# power-control-v2.net
KiCad netlist of a schematic drawn in EAGLE
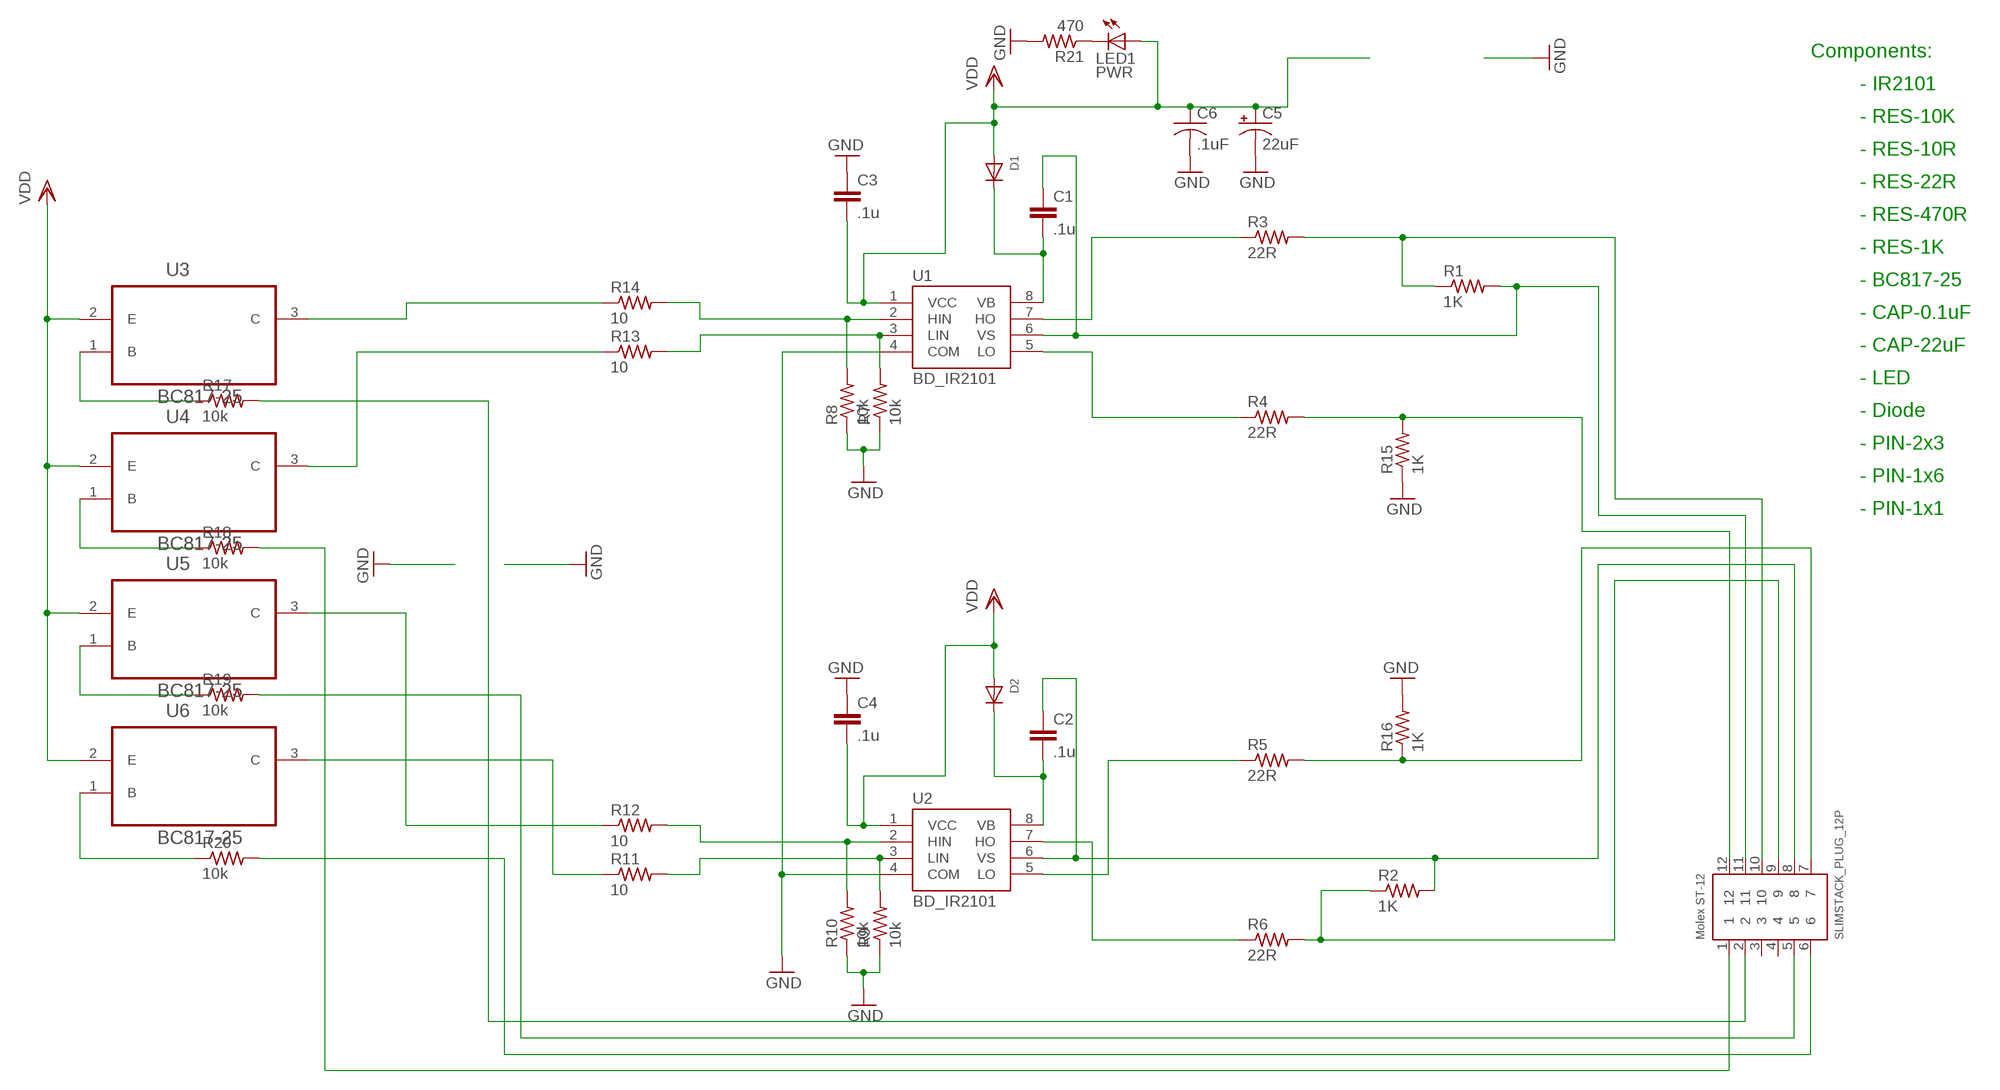
[diagram p0: schematic, sheet 1]

(export (version "E")
  (design (tool "Eeschema 10.0.6"))
  (components
    (comp (ref "C1")
      (value ".1u")
      (footprint "eagle-import:C0603")
      (libsource (lib "eagle-import") (part "C-EUC0603"))
    )
    (comp (ref "C2")
      (value ".1u")
      (footprint "eagle-import:C0603")
      (libsource (lib "eagle-import") (part "C-EUC0603"))
    )
    (comp (ref "C3")
      (value ".1u")
      (footprint "eagle-import:C0603")
      (libsource (lib "eagle-import") (part "C-EUC0603"))
    )
    (comp (ref "C4")
      (value ".1u")
      (footprint "eagle-import:C0603")
      (libsource (lib "eagle-import") (part "C-EUC0603"))
    )
    (comp (ref "C5")
      (value "22uF")
      (footprint "eagle-import:B_3528-21W")
      (libsource (lib "eagle-import") (part "CPOL-USB/3528-21W"))
    )
    (comp (ref "C6")
      (value ".1uF")
      (footprint "eagle-import:C0805")
      (libsource (lib "eagle-import") (part "C-USC0805"))
    )
    (comp (ref "D1")
      (value "DIODESOD-523")
      (footprint "eagle-import:SOD-523")
      (libsource (lib "eagle-import") (part "DIODESOD-523"))
    )
    (comp (ref "D2")
      (value "DIODESOD-523")
      (footprint "eagle-import:SOD-523")
      (libsource (lib "eagle-import") (part "DIODESOD-523"))
    )
    (comp (ref "LED1")
      (value "PWR")
      (footprint "eagle-import:CHIP-LED0805")
      (libsource (lib "eagle-import") (part "LEDCHIP-LED0805"))
    )
    (comp (ref "R1")
      (value "1K")
      (footprint "eagle-import:R0603")
      (libsource (lib "eagle-import") (part "R-US_R0603"))
    )
    (comp (ref "R2")
      (value "1K")
      (footprint "eagle-import:R0603")
      (libsource (lib "eagle-import") (part "R-US_R0603"))
    )
    (comp (ref "R3")
      (value "22R")
      (footprint "eagle-import:R0603")
      (libsource (lib "eagle-import") (part "R-US_R0603"))
    )
    (comp (ref "R4")
      (value "22R")
      (footprint "eagle-import:R0603")
      (libsource (lib "eagle-import") (part "R-US_R0603"))
    )
    (comp (ref "R5")
      (value "22R")
      (footprint "eagle-import:R0603")
      (libsource (lib "eagle-import") (part "R-US_R0603"))
    )
    (comp (ref "R6")
      (value "22R")
      (footprint "eagle-import:R0603")
      (libsource (lib "eagle-import") (part "R-US_R0603"))
    )
    (comp (ref "R7")
      (value "10k")
      (footprint "eagle-import:R0603")
      (libsource (lib "eagle-import") (part "R-US_R0603"))
    )
    (comp (ref "R8")
      (value "10k")
      (footprint "eagle-import:R0603")
      (libsource (lib "eagle-import") (part "R-US_R0603"))
    )
    (comp (ref "R9")
      (value "10k")
      (footprint "eagle-import:R0603")
      (libsource (lib "eagle-import") (part "R-US_R0603"))
    )
    (comp (ref "R10")
      (value "10k")
      (footprint "eagle-import:R0603")
      (libsource (lib "eagle-import") (part "R-US_R0603"))
    )
    (comp (ref "R11")
      (value "10")
      (footprint "eagle-import:R0603")
      (libsource (lib "eagle-import") (part "R-US_R0603"))
    )
    (comp (ref "R12")
      (value "10")
      (footprint "eagle-import:R0603")
      (libsource (lib "eagle-import") (part "R-US_R0603"))
    )
    (comp (ref "R13")
      (value "10")
      (footprint "eagle-import:R0603")
      (libsource (lib "eagle-import") (part "R-US_R0603"))
    )
    (comp (ref "R14")
      (value "10")
      (footprint "eagle-import:R0603")
      (libsource (lib "eagle-import") (part "R-US_R0603"))
    )
    (comp (ref "R15")
      (value "1K")
      (footprint "eagle-import:R0603")
      (libsource (lib "eagle-import") (part "R-US_R0603"))
    )
    (comp (ref "R16")
      (value "1K")
      (footprint "eagle-import:R0603")
      (libsource (lib "eagle-import") (part "R-US_R0603"))
    )
    (comp (ref "R17")
      (value "10k")
      (footprint "eagle-import:R0603")
      (libsource (lib "eagle-import") (part "R-US_R0603"))
    )
    (comp (ref "R18")
      (value "10k")
      (footprint "eagle-import:R0603")
      (libsource (lib "eagle-import") (part "R-US_R0603"))
    )
    (comp (ref "R19")
      (value "10k")
      (footprint "eagle-import:R0603")
      (libsource (lib "eagle-import") (part "R-US_R0603"))
    )
    (comp (ref "R20")
      (value "10k")
      (footprint "eagle-import:R0603")
      (libsource (lib "eagle-import") (part "R-US_R0603"))
    )
    (comp (ref "R21")
      (value "470")
      (footprint "eagle-import:R0603")
      (libsource (lib "eagle-import") (part "R-US_R0603"))
    )
    (comp (ref "U$1")
      (value "SLIMSTACK_PLUG_12P")
      (footprint "eagle-import:SLIMSTACK-12P")
      (libsource (lib "eagle-import") (part "SLIMSTACK_PLUG_12P"))
    )
    (comp (ref "U1")
      (value "BD_IR2101")
      (footprint "eagle-import:SO8")
      (libsource (lib "eagle-import") (part "BD_IR2101"))
    )
    (comp (ref "U2")
      (value "BD_IR2101")
      (footprint "eagle-import:SO8")
      (libsource (lib "eagle-import") (part "BD_IR2101"))
    )
    (comp (ref "U3")
      (value "BC817-25")
      (footprint "eagle-import:SOT95P240X97-3N")
      (libsource (lib "eagle-import") (part "BC817-25"))
    )
    (comp (ref "U4")
      (value "BC817-25")
      (footprint "eagle-import:SOT95P240X97-3N")
      (libsource (lib "eagle-import") (part "BC817-25"))
    )
    (comp (ref "U5")
      (value "BC817-25")
      (footprint "eagle-import:SOT95P240X97-3N")
      (libsource (lib "eagle-import") (part "BC817-25"))
    )
    (comp (ref "U6")
      (value "BC817-25")
      (footprint "eagle-import:SOT95P240X97-3N")
      (libsource (lib "eagle-import") (part "BC817-25"))
    )
  )
  (nets
    (net (code "1") (name "GND") (class "Default")
      (node (ref "C3") (pin "1") (pinfunction "1_1") (pintype "passive"))
      (node (ref "C4") (pin "1") (pinfunction "1_1") (pintype "passive"))
      (node (ref "C5") (pin "-") (pinfunction "-_-") (pintype "passive"))
      (node (ref "C6") (pin "2") (pinfunction "2_2") (pintype "passive"))
      (node (ref "R10") (pin "1") (pinfunction "1_1") (pintype "passive"))
      (node (ref "R15") (pin "1") (pinfunction "1_1") (pintype "passive"))
      (node (ref "R16") (pin "2") (pinfunction "2_2") (pintype "passive"))
      (node (ref "R21") (pin "2") (pinfunction "2_2") (pintype "passive"))
      (node (ref "R7") (pin "1") (pinfunction "1_1") (pintype "passive"))
      (node (ref "R8") (pin "1") (pinfunction "1_1") (pintype "passive"))
      (node (ref "R9") (pin "1") (pinfunction "1_1") (pintype "passive"))
      (node (ref "U1") (pin "4") (pinfunction "COM_4") (pintype "bidirectional"))
      (node (ref "U2") (pin "4") (pinfunction "COM_4") (pintype "bidirectional"))
    )
    (net (code "2") (name "Net-(D1-C)") (class "Default")
      (node (ref "C1") (pin "2") (pinfunction "2_2") (pintype "passive"))
      (node (ref "D1") (pin "K") (pinfunction "C_K") (pintype "passive"))
      (node (ref "U1") (pin "8") (pinfunction "VB_8") (pintype "bidirectional"))
    )
    (net (code "3") (name "Net-(D2-C)") (class "Default")
      (node (ref "C2") (pin "2") (pinfunction "2_2") (pintype "passive"))
      (node (ref "D2") (pin "K") (pinfunction "C_K") (pintype "passive"))
      (node (ref "U2") (pin "8") (pinfunction "VB_8") (pintype "bidirectional"))
    )
    (net (code "4") (name "Net-(LED1-PadC)") (class "Default")
      (node (ref "LED1") (pin "C") (pinfunction "C_C") (pintype "passive"))
      (node (ref "R21") (pin "1") (pinfunction "1_1") (pintype "passive"))
    )
    (net (code "5") (name "Net-(R1-Pad1)") (class "Default")
      (node (ref "R1") (pin "1") (pinfunction "1_1") (pintype "passive"))
      (node (ref "R3") (pin "2") (pinfunction "2_2") (pintype "passive"))
      (node (ref "U$1") (pin "10") (pinfunction "10_10") (pintype "bidirectional"))
    )
    (net (code "6") (name "Net-(R2-Pad1)") (class "Default")
      (node (ref "R2") (pin "1") (pinfunction "1_1") (pintype "passive"))
      (node (ref "R6") (pin "2") (pinfunction "2_2") (pintype "passive"))
      (node (ref "U$1") (pin "9") (pinfunction "9_9") (pintype "bidirectional"))
    )
    (net (code "7") (name "Net-(R15-Pad2)") (class "Default")
      (node (ref "R15") (pin "2") (pinfunction "2_2") (pintype "passive"))
      (node (ref "R4") (pin "2") (pinfunction "2_2") (pintype "passive"))
      (node (ref "U$1") (pin "12") (pinfunction "12_12") (pintype "bidirectional"))
    )
    (net (code "8") (name "Net-(R16-Pad1)") (class "Default")
      (node (ref "R16") (pin "1") (pinfunction "1_1") (pintype "passive"))
      (node (ref "R5") (pin "2") (pinfunction "2_2") (pintype "passive"))
      (node (ref "U$1") (pin "7") (pinfunction "7_7") (pintype "bidirectional"))
    )
    (net (code "9") (name "Net-(R17-Pad2)") (class "Default")
      (node (ref "R17") (pin "2") (pinfunction "2_2") (pintype "passive"))
      (node (ref "U$1") (pin "2") (pinfunction "2_2") (pintype "bidirectional"))
    )
    (net (code "10") (name "Net-(R18-Pad2)") (class "Default")
      (node (ref "R18") (pin "2") (pinfunction "2_2") (pintype "passive"))
      (node (ref "U$1") (pin "1") (pinfunction "1_1") (pintype "bidirectional"))
    )
    (net (code "11") (name "Net-(R19-Pad2)") (class "Default")
      (node (ref "R19") (pin "2") (pinfunction "2_2") (pintype "passive"))
      (node (ref "U$1") (pin "5") (pinfunction "5_5") (pintype "bidirectional"))
    )
    (net (code "12") (name "Net-(R20-Pad2)") (class "Default")
      (node (ref "R20") (pin "2") (pinfunction "2_2") (pintype "passive"))
      (node (ref "U$1") (pin "6") (pinfunction "6_6") (pintype "bidirectional"))
    )
    (net (code "13") (name "Net-(U1-HIN)") (class "Default")
      (node (ref "R14") (pin "2") (pinfunction "2_2") (pintype "passive"))
      (node (ref "R8") (pin "2") (pinfunction "2_2") (pintype "passive"))
      (node (ref "U1") (pin "2") (pinfunction "HIN_2") (pintype "bidirectional"))
    )
    (net (code "14") (name "Net-(U1-HO)") (class "Default")
      (node (ref "R3") (pin "1") (pinfunction "1_1") (pintype "passive"))
      (node (ref "U1") (pin "7") (pinfunction "HO_7") (pintype "bidirectional"))
    )
    (net (code "15") (name "Net-(U1-LIN)") (class "Default")
      (node (ref "R13") (pin "2") (pinfunction "2_2") (pintype "passive"))
      (node (ref "R7") (pin "2") (pinfunction "2_2") (pintype "passive"))
      (node (ref "U1") (pin "3") (pinfunction "LIN_3") (pintype "bidirectional"))
    )
    (net (code "16") (name "Net-(U1-LO)") (class "Default")
      (node (ref "R4") (pin "1") (pinfunction "1_1") (pintype "passive"))
      (node (ref "U1") (pin "5") (pinfunction "LO_5") (pintype "bidirectional"))
    )
    (net (code "17") (name "Net-(U1-VS)") (class "Default")
      (node (ref "C1") (pin "1") (pinfunction "1_1") (pintype "passive"))
      (node (ref "R1") (pin "2") (pinfunction "2_2") (pintype "passive"))
      (node (ref "U$1") (pin "11") (pinfunction "11_11") (pintype "bidirectional"))
      (node (ref "U1") (pin "6") (pinfunction "VS_6") (pintype "bidirectional"))
    )
    (net (code "18") (name "Net-(U2-HIN)") (class "Default")
      (node (ref "R10") (pin "2") (pinfunction "2_2") (pintype "passive"))
      (node (ref "R12") (pin "2") (pinfunction "2_2") (pintype "passive"))
      (node (ref "U2") (pin "2") (pinfunction "HIN_2") (pintype "bidirectional"))
    )
    (net (code "19") (name "Net-(U2-HO)") (class "Default")
      (node (ref "R6") (pin "1") (pinfunction "1_1") (pintype "passive"))
      (node (ref "U2") (pin "7") (pinfunction "HO_7") (pintype "bidirectional"))
    )
    (net (code "20") (name "Net-(U2-LIN)") (class "Default")
      (node (ref "R11") (pin "2") (pinfunction "2_2") (pintype "passive"))
      (node (ref "R9") (pin "2") (pinfunction "2_2") (pintype "passive"))
      (node (ref "U2") (pin "3") (pinfunction "LIN_3") (pintype "bidirectional"))
    )
    (net (code "21") (name "Net-(U2-LO)") (class "Default")
      (node (ref "R5") (pin "1") (pinfunction "1_1") (pintype "passive"))
      (node (ref "U2") (pin "5") (pinfunction "LO_5") (pintype "bidirectional"))
    )
    (net (code "22") (name "Net-(U2-VS)") (class "Default")
      (node (ref "C2") (pin "1") (pinfunction "1_1") (pintype "passive"))
      (node (ref "R2") (pin "2") (pinfunction "2_2") (pintype "passive"))
      (node (ref "U$1") (pin "8") (pinfunction "8_8") (pintype "bidirectional"))
      (node (ref "U2") (pin "6") (pinfunction "VS_6") (pintype "bidirectional"))
    )
    (net (code "23") (name "Net-(U3-B)") (class "Default")
      (node (ref "R17") (pin "1") (pinfunction "1_1") (pintype "passive"))
      (node (ref "U3") (pin "1") (pinfunction "B_1") (pintype "passive"))
    )
    (net (code "24") (name "Net-(U3-C)") (class "Default")
      (node (ref "R14") (pin "1") (pinfunction "1_1") (pintype "passive"))
      (node (ref "U3") (pin "3") (pinfunction "C_3") (pintype "passive"))
    )
    (net (code "25") (name "Net-(U4-B)") (class "Default")
      (node (ref "R18") (pin "1") (pinfunction "1_1") (pintype "passive"))
      (node (ref "U4") (pin "1") (pinfunction "B_1") (pintype "passive"))
    )
    (net (code "26") (name "Net-(U4-C)") (class "Default")
      (node (ref "R13") (pin "1") (pinfunction "1_1") (pintype "passive"))
      (node (ref "U4") (pin "3") (pinfunction "C_3") (pintype "passive"))
    )
    (net (code "27") (name "Net-(U5-B)") (class "Default")
      (node (ref "R19") (pin "1") (pinfunction "1_1") (pintype "passive"))
      (node (ref "U5") (pin "1") (pinfunction "B_1") (pintype "passive"))
    )
    (net (code "28") (name "Net-(U5-C)") (class "Default")
      (node (ref "R12") (pin "1") (pinfunction "1_1") (pintype "passive"))
      (node (ref "U5") (pin "3") (pinfunction "C_3") (pintype "passive"))
    )
    (net (code "29") (name "Net-(U6-B)") (class "Default")
      (node (ref "R20") (pin "1") (pinfunction "1_1") (pintype "passive"))
      (node (ref "U6") (pin "1") (pinfunction "B_1") (pintype "passive"))
    )
    (net (code "30") (name "Net-(U6-C)") (class "Default")
      (node (ref "R11") (pin "1") (pinfunction "1_1") (pintype "passive"))
      (node (ref "U6") (pin "3") (pinfunction "C_3") (pintype "passive"))
    )
    (net (code "31") (name "VDD") (class "Default")
      (node (ref "C3") (pin "2") (pinfunction "2_2") (pintype "passive"))
      (node (ref "C4") (pin "2") (pinfunction "2_2") (pintype "passive"))
      (node (ref "C5") (pin "+") (pinfunction "+_+") (pintype "passive"))
      (node (ref "C6") (pin "1") (pinfunction "1_1") (pintype "passive"))
      (node (ref "D1") (pin "A") (pinfunction "A_A") (pintype "passive"))
      (node (ref "D2") (pin "A") (pinfunction "A_A") (pintype "passive"))
      (node (ref "LED1") (pin "A") (pinfunction "A_A") (pintype "passive"))
      (node (ref "U1") (pin "1") (pinfunction "VCC_1") (pintype "bidirectional"))
      (node (ref "U2") (pin "1") (pinfunction "VCC_1") (pintype "bidirectional"))
      (node (ref "U3") (pin "2") (pinfunction "E_2") (pintype "passive"))
      (node (ref "U4") (pin "2") (pinfunction "E_2") (pintype "passive"))
      (node (ref "U5") (pin "2") (pinfunction "E_2") (pintype "passive"))
      (node (ref "U6") (pin "2") (pinfunction "E_2") (pintype "passive"))
    )
    (net (code "32") (name "unconnected-(U$1-Pad3)") (class "Default")
      (node (ref "U$1") (pin "3") (pinfunction "3_3") (pintype "bidirectional"))
    )
    (net (code "33") (name "unconnected-(U$1-Pad4)") (class "Default")
      (node (ref "U$1") (pin "4") (pinfunction "4_4") (pintype "bidirectional"))
    )
  )
)
